# gyroscope.net
KiCad netlist of a schematic drawn in Altium Designer
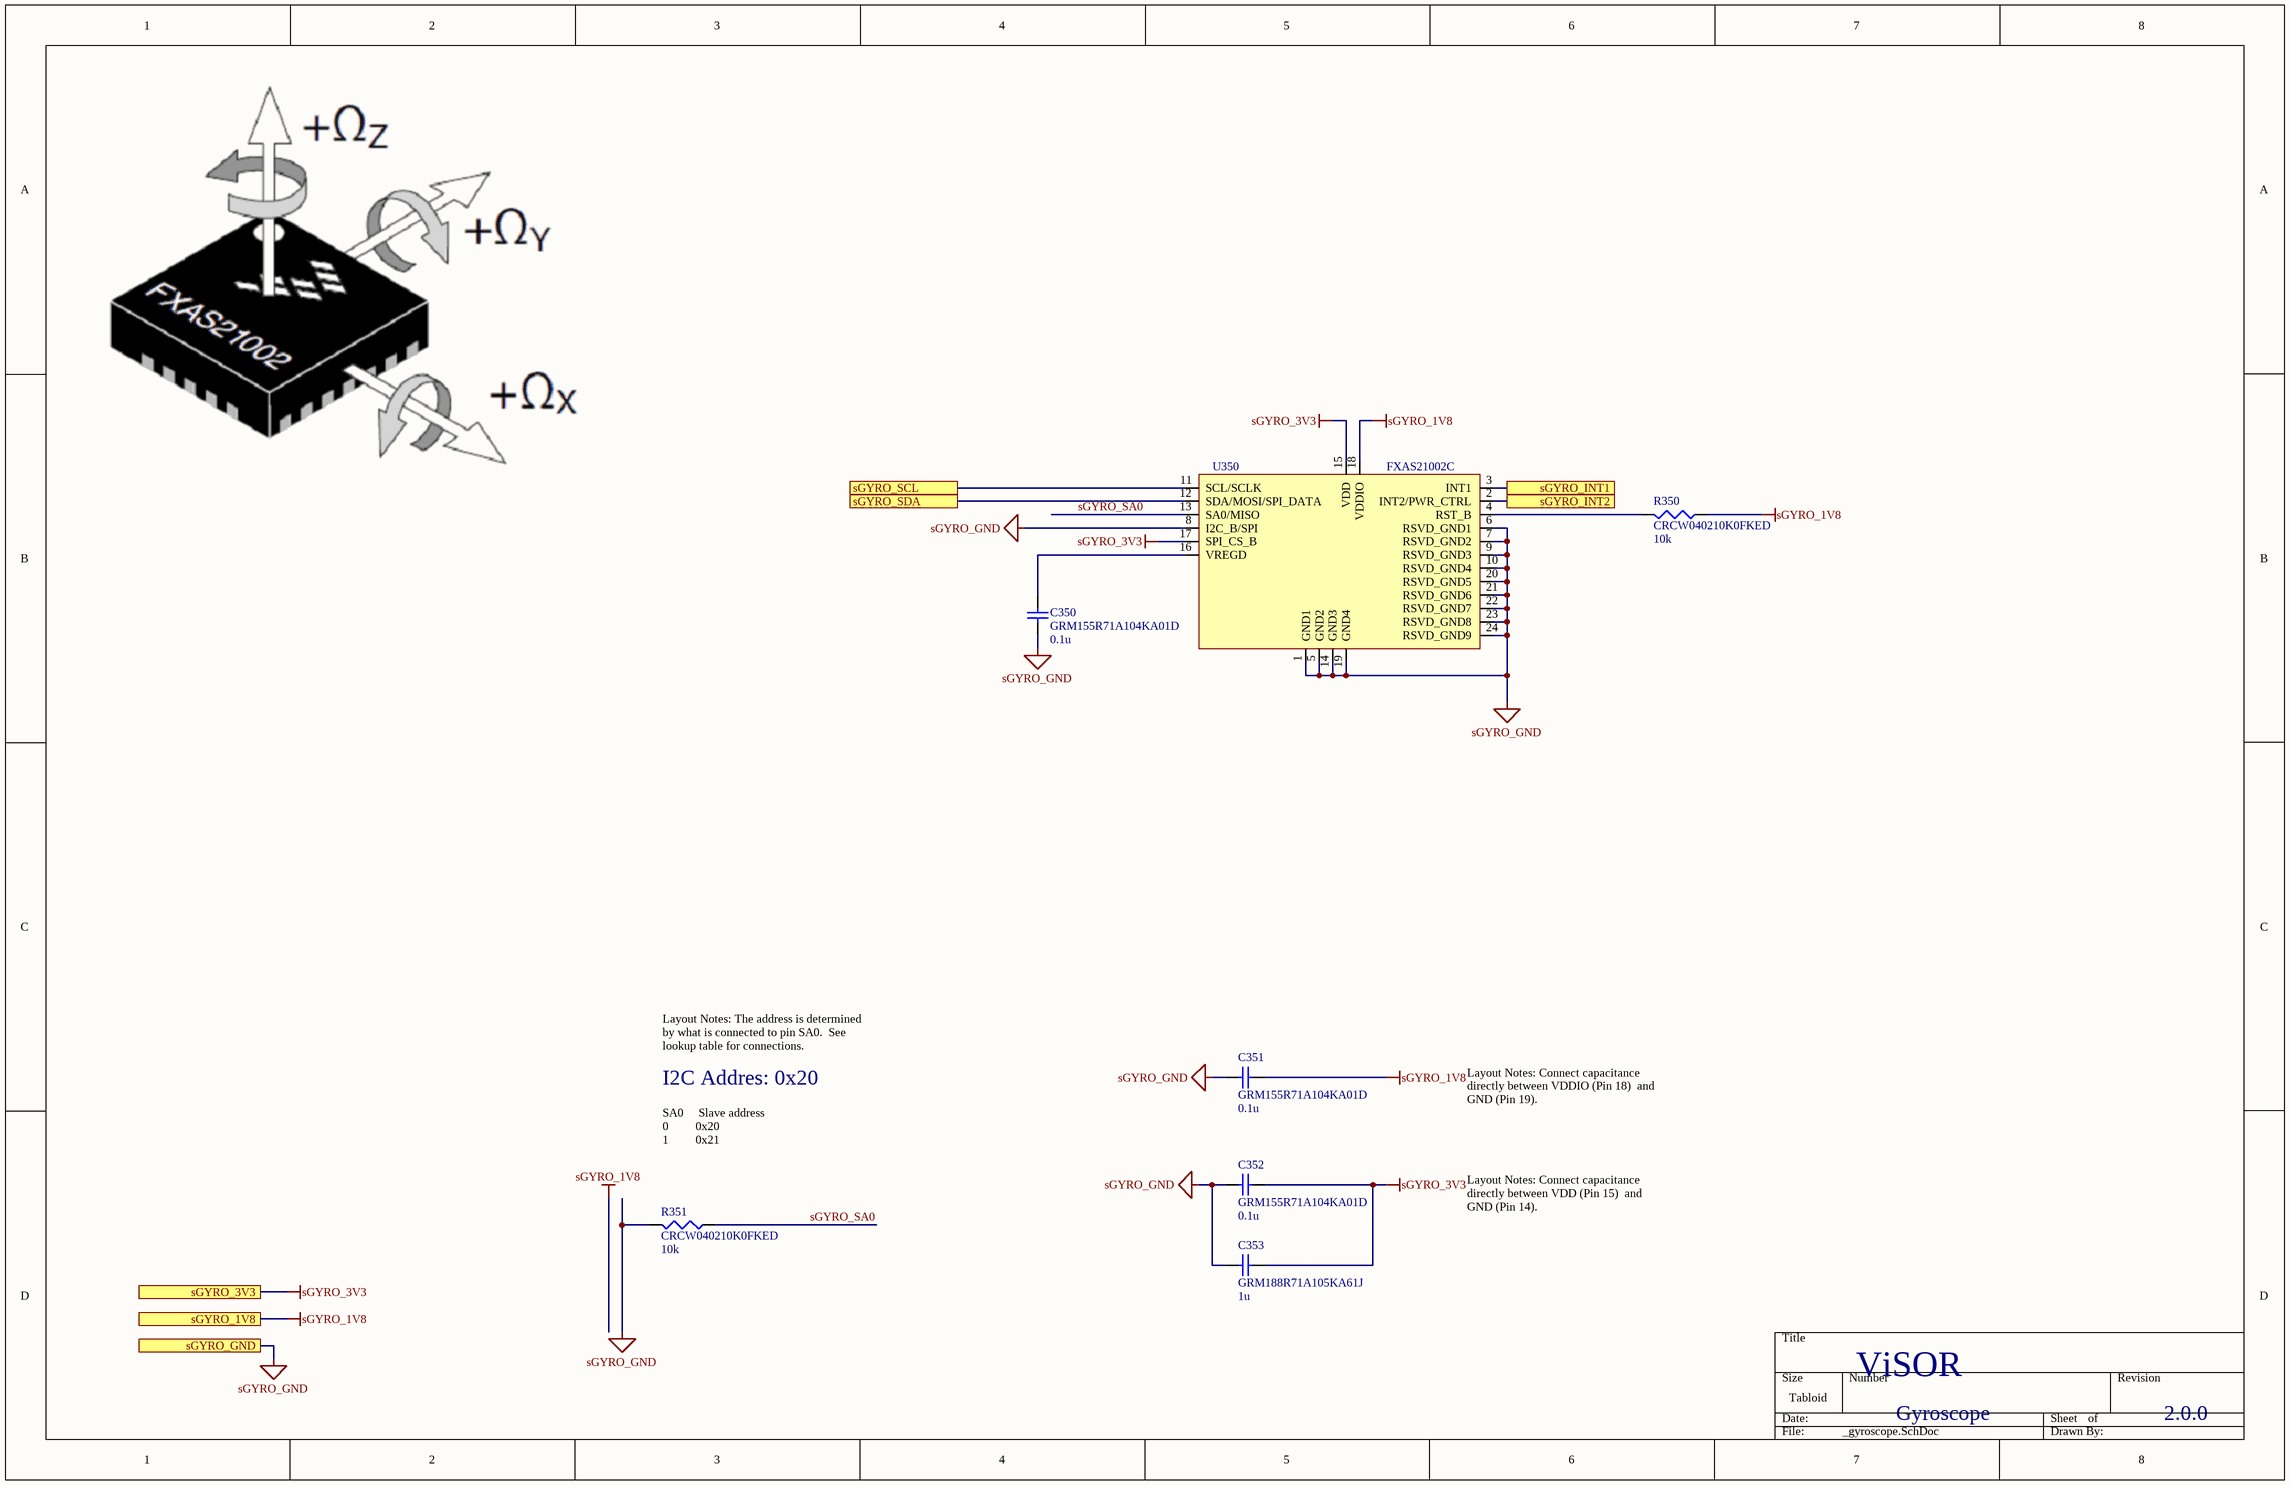
[diagram p0: _gyroscope.SchDoc]

(export (version "E")
  (design (tool "Eeschema 10.0.6"))
  (components
    (comp (ref "C350")
      (value "GRM155R71A104KA01D")
      (footprint "0402")
      (description "-55-125C, 1005, 10V, X7R, ±10%")
      (fields (field (name "ALTIUM_VALUE") "0.1u"))
      (libsource (lib "standard_capacitors") (part "GRM155R71AxxxKdddd"))
    )
    (comp (ref "C351")
      (value "GRM155R71A104KA01D")
      (footprint "0402")
      (description "-55-125C, 1005, 10V, X7R, ±10%")
      (fields (field (name "ALTIUM_VALUE") "0.1u"))
      (libsource (lib "standard_capacitors") (part "GRM155R71AxxxKdddd"))
    )
    (comp (ref "C352")
      (value "GRM155R71A104KA01D")
      (footprint "0402")
      (description "-55-125C, 1005, 10V, X7R, ±10%")
      (fields (field (name "ALTIUM_VALUE") "0.1u"))
      (libsource (lib "standard_capacitors") (part "GRM155R71AxxxKdddd"))
    )
    (comp (ref "C353")
      (value "GRM188R71A105KA61J")
      (footprint "0603")
      (description "-55-125C, 1608, 10V, X7R, ±10%")
      (fields (field (name "ALTIUM_VALUE") "1u"))
      (libsource (lib "standard_capacitors") (part "GRM188R71AxxxKdddd"))
    )
    (comp (ref "R350")
      (value "CRCW040210K0FKED")
      (footprint "0402")
      (description "0.125W, -55-155C, 1005, 50V, ±1%")
      (fields (field (name "ALTIUM_VALUE") "10k"))
      (libsource (lib "standard_resistors") (part "CRCW0402xxxxFKED"))
    )
    (comp (ref "R351")
      (value "CRCW040210K0FKED")
      (footprint "0402")
      (description "0.125W, -55-155C, 1005, 50V, ±1%")
      (fields (field (name "ALTIUM_VALUE") "10k"))
      (libsource (lib "standard_resistors") (part "CRCW0402xxxxFKED"))
    )
    (comp (ref "U350")
      (value "FXAS21002C")
      (footprint "SMD QFN 24_4X4MM 7/5")
      (description "3-Axis Digital Angular Rate  Gyroscope")
      (libsource (lib "nxp") (part "FXAS21002C"))
    )
  )
  (nets
    (net (code "1") (name "/sGYRO_INT1") (class "Default")
      (node (ref "U350") (pin "3") (pinfunction "INT1_3") (pintype "passive"))
    )
    (net (code "2") (name "/sGYRO_INT2") (class "Default")
      (node (ref "U350") (pin "2") (pinfunction "INT2/PWR_CTRL_2") (pintype "passive"))
    )
    (net (code "3") (name "/sGYRO_SA0") (class "Default")
      (node (ref "R351") (pin "1") (pinfunction "1_1") (pintype "passive"))
      (node (ref "U350") (pin "13") (pinfunction "SA0/MISO_13") (pintype "passive"))
    )
    (net (code "4") (name "/sGYRO_SCL") (class "Default")
      (node (ref "U350") (pin "11") (pinfunction "SCL/SCLK_11") (pintype "passive"))
    )
    (net (code "5") (name "/sGYRO_SDA") (class "Default")
      (node (ref "U350") (pin "12") (pinfunction "SDA/MOSI/SPI_DATA_12") (pintype "passive"))
    )
    (net (code "6") (name "Net-(U350-RST_B)") (class "Default")
      (node (ref "R350") (pin "2") (pinfunction "2_2") (pintype "passive"))
      (node (ref "U350") (pin "4") (pinfunction "RST_B_4") (pintype "passive"))
    )
    (net (code "7") (name "Net-(U350-VREGD)") (class "Default")
      (node (ref "C350") (pin "1") (pinfunction "1_1") (pintype "passive"))
      (node (ref "U350") (pin "16") (pinfunction "VREGD_16") (pintype "passive"))
    )
    (net (code "8") (name "sGYRO_1V8") (class "Default")
      (node (ref "C351") (pin "2") (pinfunction "2_2") (pintype "passive"))
      (node (ref "R350") (pin "1") (pinfunction "1_1") (pintype "passive"))
      (node (ref "U350") (pin "18") (pinfunction "VDDIO_18") (pintype "passive"))
    )
    (net (code "9") (name "sGYRO_3V3") (class "Default")
      (node (ref "C352") (pin "2") (pinfunction "2_2") (pintype "passive"))
      (node (ref "C353") (pin "1") (pinfunction "1_1") (pintype "passive"))
      (node (ref "U350") (pin "15") (pinfunction "VDD_15") (pintype "passive"))
      (node (ref "U350") (pin "17") (pinfunction "SPI_CS_B_17") (pintype "passive"))
    )
    (net (code "10") (name "sGYRO_GND") (class "Default")
      (node (ref "C350") (pin "2") (pinfunction "2_2") (pintype "passive"))
      (node (ref "C351") (pin "1") (pinfunction "1_1") (pintype "passive"))
      (node (ref "C352") (pin "1") (pinfunction "1_1") (pintype "passive"))
      (node (ref "C353") (pin "2") (pinfunction "2_2") (pintype "passive"))
      (node (ref "R351") (pin "2") (pinfunction "2_2") (pintype "passive"))
      (node (ref "U350") (pin "1") (pinfunction "GND1_1") (pintype "passive"))
      (node (ref "U350") (pin "10") (pinfunction "RSVD_GND4_10") (pintype "passive"))
      (node (ref "U350") (pin "14") (pinfunction "GND3_14") (pintype "passive"))
      (node (ref "U350") (pin "19") (pinfunction "GND4_19") (pintype "passive"))
      (node (ref "U350") (pin "20") (pinfunction "RSVD_GND5_20") (pintype "passive"))
      (node (ref "U350") (pin "21") (pinfunction "RSVD_GND6_21") (pintype "passive"))
      (node (ref "U350") (pin "22") (pinfunction "RSVD_GND7_22") (pintype "passive"))
      (node (ref "U350") (pin "23") (pinfunction "RSVD_GND8_23") (pintype "passive"))
      (node (ref "U350") (pin "24") (pinfunction "RSVD_GND9_24") (pintype "passive"))
      (node (ref "U350") (pin "5") (pinfunction "GND2_5") (pintype "passive"))
      (node (ref "U350") (pin "6") (pinfunction "RSVD_GND1_6") (pintype "passive"))
      (node (ref "U350") (pin "7") (pinfunction "RSVD_GND2_7") (pintype "passive"))
      (node (ref "U350") (pin "8") (pinfunction "I2C_B/SPI_8") (pintype "passive"))
      (node (ref "U350") (pin "9") (pinfunction "RSVD_GND3_9") (pintype "passive"))
    )
  )
)
